# battery-board.net
KiCad netlist of a schematic drawn in EAGLE
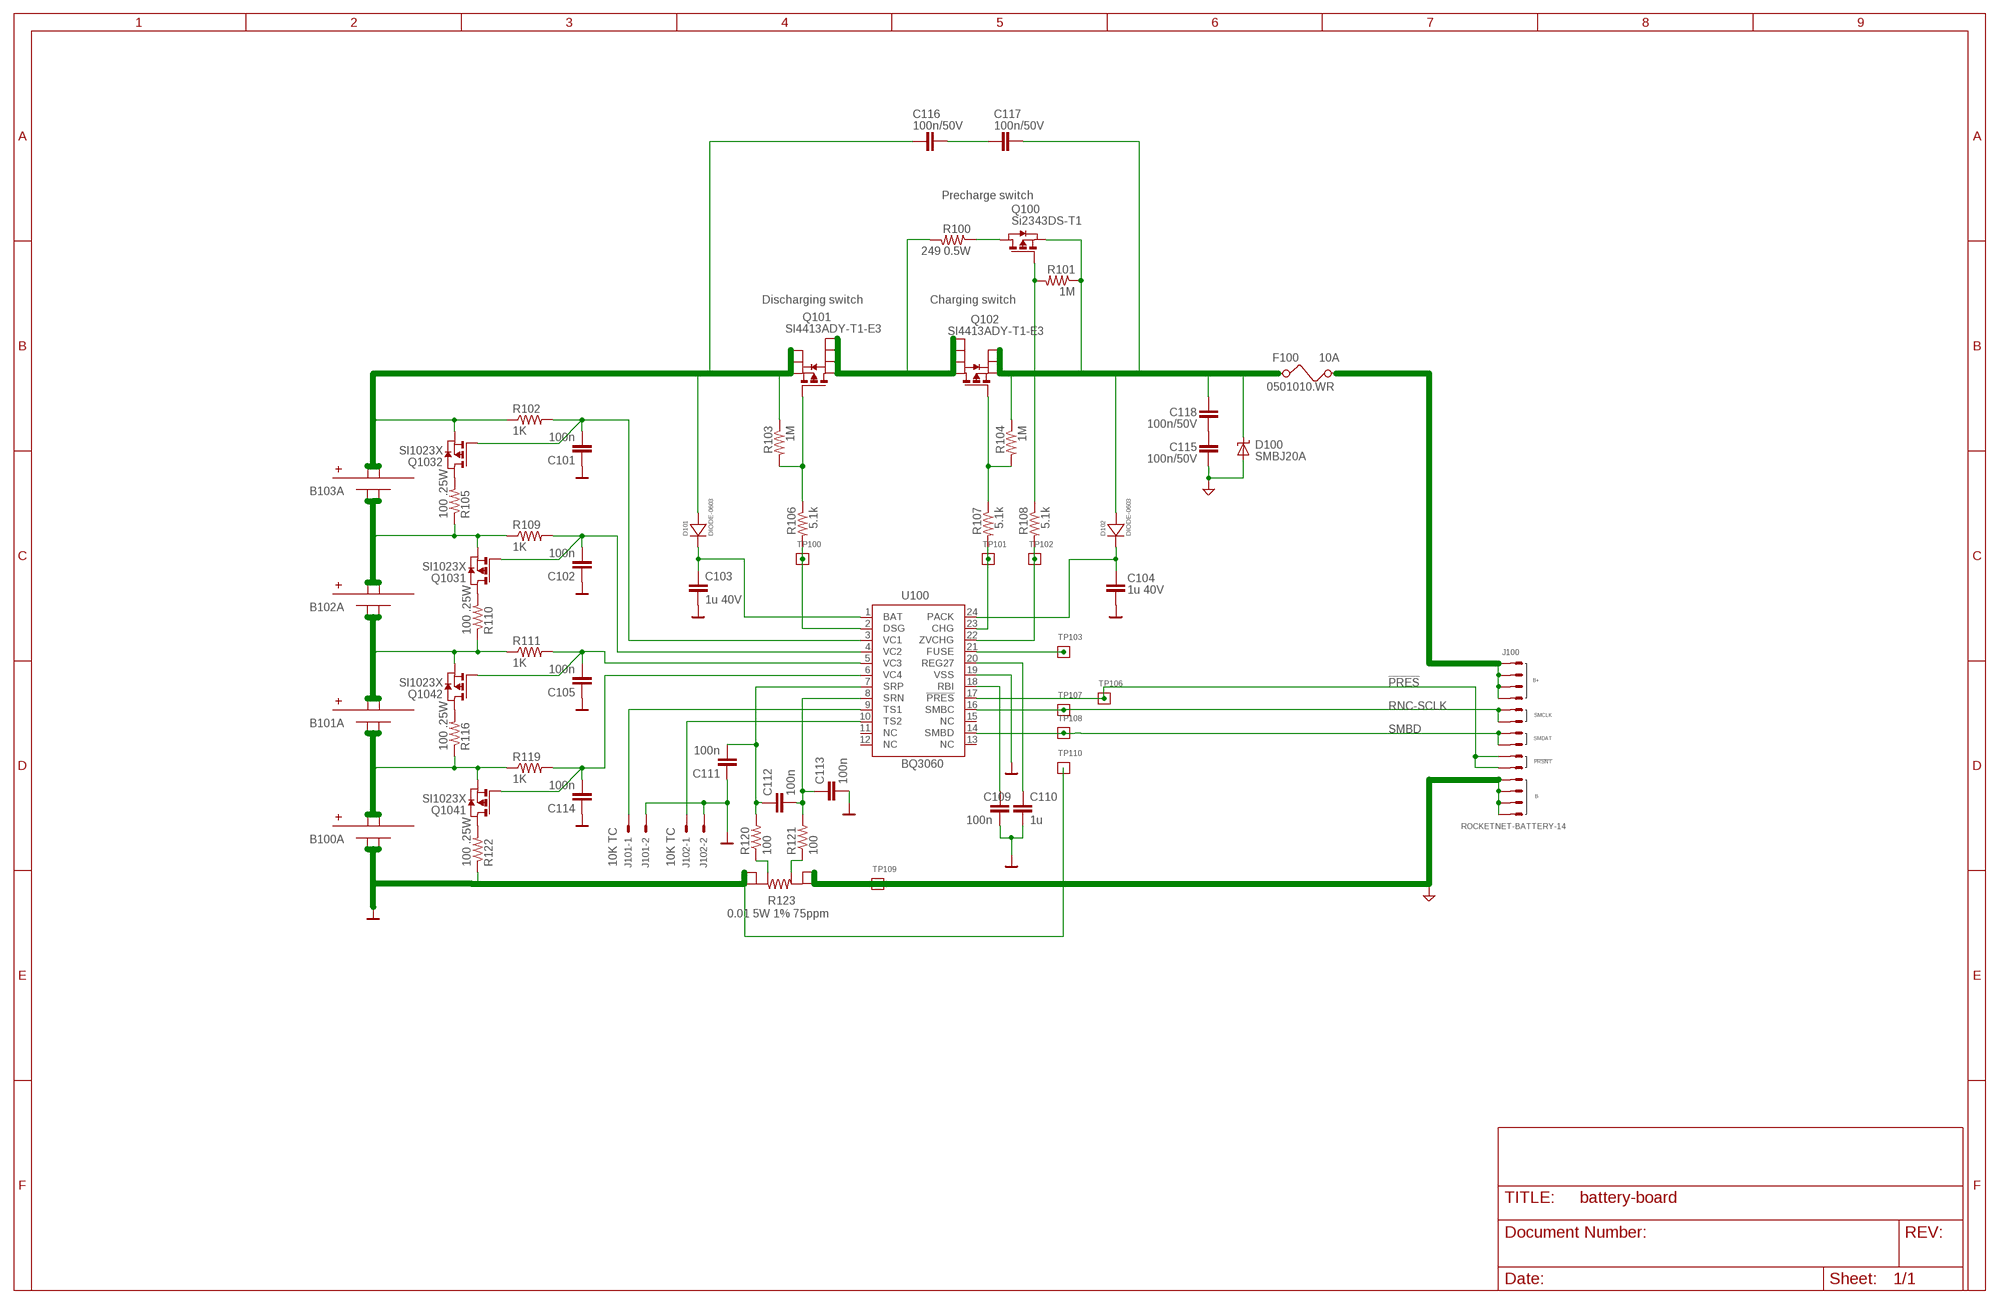
[diagram p0: schematic, sheet 1]

(export (version "E")
  (design (tool "Eeschema 10.0.6"))
  (components
    (comp (ref "B100A")
      (value "LIPO-8AHR")
      (footprint "eagle-import:LIPO-8AHR-PAC")
      (libsource (lib "eagle-import") (part "LIPO-8AHR"))
    )
    (comp (ref "B101A")
      (value "LIPO-8AHR")
      (footprint "eagle-import:LIPO-8AHR-PAC")
      (libsource (lib "eagle-import") (part "LIPO-8AHR"))
    )
    (comp (ref "B102A")
      (value "LIPO-8AHR")
      (footprint "eagle-import:LIPO-8AHR-PAC")
      (libsource (lib "eagle-import") (part "LIPO-8AHR"))
    )
    (comp (ref "B103A")
      (value "LIPO-8AHR")
      (footprint "eagle-import:LIPO-8AHR-PAC")
      (libsource (lib "eagle-import") (part "LIPO-8AHR"))
    )
    (comp (ref "C101")
      (value "100n")
      (footprint "eagle-import:0603-B-NOSILK")
      (libsource (lib "eagle-import") (part "C-EU0603-B-NOSILK"))
    )
    (comp (ref "C102")
      (value "100n")
      (footprint "eagle-import:0603-B-NOSILK")
      (libsource (lib "eagle-import") (part "C-EU0603-B-NOSILK"))
    )
    (comp (ref "C103")
      (value "1u 40V")
      (footprint "eagle-import:0603-B-NOSILK")
      (libsource (lib "eagle-import") (part "C-EU0603-B-NOSILK"))
    )
    (comp (ref "C104")
      (value "1u 40V")
      (footprint "eagle-import:0603-B-NOSILK")
      (libsource (lib "eagle-import") (part "C-EU0603-B-NOSILK"))
    )
    (comp (ref "C105")
      (value "100n")
      (footprint "eagle-import:0603-B-NOSILK")
      (libsource (lib "eagle-import") (part "C-EU0603-B-NOSILK"))
    )
    (comp (ref "C109")
      (value "100n")
      (footprint "eagle-import:0603-B-NOSILK")
      (libsource (lib "eagle-import") (part "C-EU0603-B-NOSILK"))
    )
    (comp (ref "C110")
      (value "1u")
      (footprint "eagle-import:0603-B-NOSILK")
      (libsource (lib "eagle-import") (part "C-EU0603-B-NOSILK"))
    )
    (comp (ref "C111")
      (value "100n")
      (footprint "eagle-import:0603-B-NOSILK")
      (libsource (lib "eagle-import") (part "C-EU0603-B-NOSILK"))
    )
    (comp (ref "C112")
      (value "100n")
      (footprint "eagle-import:0603-B-NOSILK")
      (libsource (lib "eagle-import") (part "C-EU0603-B-NOSILK"))
    )
    (comp (ref "C113")
      (value "100n")
      (footprint "eagle-import:0603-B-NOSILK")
      (libsource (lib "eagle-import") (part "C-EU0603-B-NOSILK"))
    )
    (comp (ref "C114")
      (value "100n")
      (footprint "eagle-import:0603-B-NOSILK")
      (libsource (lib "eagle-import") (part "C-EU0603-B-NOSILK"))
    )
    (comp (ref "C115")
      (value "100n/50V")
      (footprint "eagle-import:0603-B-NOSILK")
      (libsource (lib "eagle-import") (part "C-EU0603-B-NOSILK"))
    )
    (comp (ref "C116")
      (value "100n/50V")
      (footprint "eagle-import:0603-B-NOSILK")
      (libsource (lib "eagle-import") (part "C-EU0603-B-NOSILK"))
    )
    (comp (ref "C117")
      (value "100n/50V")
      (footprint "eagle-import:0603-B-NOSILK")
      (libsource (lib "eagle-import") (part "C-EU0603-B-NOSILK"))
    )
    (comp (ref "C118")
      (value "100n/50V")
      (footprint "eagle-import:0603-B-NOSILK")
      (libsource (lib "eagle-import") (part "C-EU0603-B-NOSILK"))
    )
    (comp (ref "D100")
      (value "SMBJ20A")
      (footprint "eagle-import:SMBJ")
      (libsource (lib "eagle-import") (part "SUPPRESSOR-SMBJ"))
    )
    (comp (ref "D101")
      (value "DIODE-0603")
      (footprint "eagle-import:0603-B-NOSILK-DIODE")
      (libsource (lib "eagle-import") (part "DIODE-0603"))
    )
    (comp (ref "D102")
      (value "DIODE-0603")
      (footprint "eagle-import:0603-B-NOSILK-DIODE")
      (libsource (lib "eagle-import") (part "DIODE-0603"))
    )
    (comp (ref "F100")
      (value "0501010.WR")
      (footprint "eagle-import:1206")
      (fields (field (name "DK") "F2919CT-ND"))
      (libsource (lib "eagle-import") (part "FUSE1206"))
    )
    (comp (ref "J100")
      (value "ROCKETNET-BATTERY-14")
      (footprint "eagle-import:ROCKETNET-M-14")
      (libsource (lib "eagle-import") (part "ROCKETNET-BATTERY-14"))
    )
    (comp (ref "J101")
      (value "87758-0216")
      (footprint "eagle-import:87758-0216")
      (libsource (lib "eagle-import") (part "87758-0216"))
    )
    (comp (ref "J102")
      (value "87758-0216")
      (footprint "eagle-import:87758-0216")
      (libsource (lib "eagle-import") (part "87758-0216"))
    )
    (comp (ref "Q100")
      (value "Si2343DS-T1")
      (footprint "eagle-import:SOT23")
      (libsource (lib "eagle-import") (part "NTR4101P"))
    )
    (comp (ref "Q101")
      (value "SI4413ADY-T1-E3")
      (footprint "eagle-import:SO-8")
      (libsource (lib "eagle-import") (part "SI4435DDY"))
    )
    (comp (ref "Q102")
      (value "SI4413ADY-T1-E3")
      (footprint "eagle-import:SO-8")
      (libsource (lib "eagle-import") (part "SI4435DDY"))
    )
    (comp (ref "Q103")
      (value "SI1023X")
      (footprint "eagle-import:SOT-563")
      (libsource (lib "eagle-import") (part "SI1023X"))
    )
    (comp (ref "Q104")
      (value "SI1023X")
      (footprint "eagle-import:SOT-563")
      (libsource (lib "eagle-import") (part "SI1023X"))
    )
    (comp (ref "R100")
      (value "249 0.5W")
      (footprint "eagle-import:1206-B")
      (libsource (lib "eagle-import") (part "R-US_1206-B"))
    )
    (comp (ref "R101")
      (value "1M")
      (footprint "eagle-import:0603-B-NOSILK")
      (libsource (lib "eagle-import") (part "R-US_0603-B-NOSILK"))
    )
    (comp (ref "R102")
      (value "1K")
      (footprint "eagle-import:0603-B-NOSILK")
      (libsource (lib "eagle-import") (part "R-US_0603-B-NOSILK"))
    )
    (comp (ref "R103")
      (value "1M")
      (footprint "eagle-import:0603-B-NOSILK")
      (libsource (lib "eagle-import") (part "R-US_0603-B-NOSILK"))
    )
    (comp (ref "R104")
      (value "1M")
      (footprint "eagle-import:0603-B-NOSILK")
      (libsource (lib "eagle-import") (part "R-US_0603-B-NOSILK"))
    )
    (comp (ref "R105")
      (value "100 .25W")
      (footprint "eagle-import:0603-B-NOSILK")
      (libsource (lib "eagle-import") (part "R-US_0603-B-NOSILK"))
    )
    (comp (ref "R106")
      (value "5.1k")
      (footprint "eagle-import:0603-B-NOSILK")
      (libsource (lib "eagle-import") (part "R-US_0603-B-NOSILK"))
    )
    (comp (ref "R107")
      (value "5.1k")
      (footprint "eagle-import:0603-B-NOSILK")
      (libsource (lib "eagle-import") (part "R-US_0603-B-NOSILK"))
    )
    (comp (ref "R108")
      (value "5.1k")
      (footprint "eagle-import:0603-B-NOSILK")
      (libsource (lib "eagle-import") (part "R-US_0603-B-NOSILK"))
    )
    (comp (ref "R109")
      (value "1K")
      (footprint "eagle-import:0603-B-NOSILK")
      (libsource (lib "eagle-import") (part "R-US_0603-B-NOSILK"))
    )
    (comp (ref "R110")
      (value "100 .25W")
      (footprint "eagle-import:0603-B-NOSILK")
      (libsource (lib "eagle-import") (part "R-US_0603-B-NOSILK"))
    )
    (comp (ref "R111")
      (value "1K")
      (footprint "eagle-import:0603-B-NOSILK")
      (libsource (lib "eagle-import") (part "R-US_0603-B-NOSILK"))
    )
    (comp (ref "R116")
      (value "100 .25W")
      (footprint "eagle-import:0603-B-NOSILK")
      (libsource (lib "eagle-import") (part "R-US_0603-B-NOSILK"))
    )
    (comp (ref "R119")
      (value "1K")
      (footprint "eagle-import:0603-B-NOSILK")
      (libsource (lib "eagle-import") (part "R-US_0603-B-NOSILK"))
    )
    (comp (ref "R120")
      (value "100")
      (footprint "eagle-import:0603-B-NOSILK")
      (libsource (lib "eagle-import") (part "R-US_0603-B-NOSILK"))
    )
    (comp (ref "R121")
      (value "100")
      (footprint "eagle-import:0603-B-NOSILK")
      (libsource (lib "eagle-import") (part "R-US_0603-B-NOSILK"))
    )
    (comp (ref "R122")
      (value "100 .25W")
      (footprint "eagle-import:0603-B-NOSILK")
      (libsource (lib "eagle-import") (part "R-US_0603-B-NOSILK"))
    )
    (comp (ref "R123")
      (value "0.01 5W 1% 75ppm")
      (footprint "eagle-import:VISHAY-2818")
      (libsource (lib "eagle-import") (part "R-US-2818"))
    )
    (comp (ref "TP100")
      (value "TEST-POINT")
      (footprint "eagle-import:2MM-TEST-POINT")
      (libsource (lib "eagle-import") (part "TEST-POINT"))
    )
    (comp (ref "TP101")
      (value "TEST-POINT")
      (footprint "eagle-import:2MM-TEST-POINT")
      (libsource (lib "eagle-import") (part "TEST-POINT"))
    )
    (comp (ref "TP102")
      (value "TEST-POINT")
      (footprint "eagle-import:2MM-TEST-POINT")
      (libsource (lib "eagle-import") (part "TEST-POINT"))
    )
    (comp (ref "TP103")
      (value "TEST-POINT")
      (footprint "eagle-import:2MM-TEST-POINT")
      (libsource (lib "eagle-import") (part "TEST-POINT"))
    )
    (comp (ref "TP106")
      (value "TEST-POINT")
      (footprint "eagle-import:2MM-TEST-POINT")
      (libsource (lib "eagle-import") (part "TEST-POINT"))
    )
    (comp (ref "TP107")
      (value "TEST-POINT")
      (footprint "eagle-import:2MM-TEST-POINT")
      (libsource (lib "eagle-import") (part "TEST-POINT"))
    )
    (comp (ref "TP108")
      (value "TEST-POINT")
      (footprint "eagle-import:2MM-TEST-POINT")
      (libsource (lib "eagle-import") (part "TEST-POINT"))
    )
    (comp (ref "TP109")
      (value "TEST-POINT")
      (footprint "eagle-import:2MM-TEST-POINT")
      (libsource (lib "eagle-import") (part "TEST-POINT"))
    )
    (comp (ref "TP110")
      (value "TEST-POINT")
      (footprint "eagle-import:2MM-TEST-POINT")
      (libsource (lib "eagle-import") (part "TEST-POINT"))
    )
    (comp (ref "U100")
      (value "BQ3060PW")
      (footprint "eagle-import:PW-R-PDSO-G24")
      (libsource (lib "eagle-import") (part "BQ3060PW"))
    )
  )
  (nets
    (net (code "1") (name "/RNC-SCLK") (class "Default")
      (node (ref "J100") (pin "SMCLK@3") (pinfunction "SMCLK_SMCLK@3") (pintype "passive"))
      (node (ref "J100") (pin "SMCLK@4") (pinfunction "SMCLK_SMCLK@4") (pintype "passive"))
      (node (ref "TP107") (pin "1") (pinfunction "P$1_1") (pintype "passive"))
      (node (ref "U100") (pin "16") (pinfunction "SMBC_16") (pintype "bidirectional"))
    )
    (net (code "2") (name "/SMBD") (class "Default")
      (node (ref "J100") (pin "SMDAT@7") (pinfunction "SMDAT_SMDAT@7") (pintype "passive"))
      (node (ref "J100") (pin "SMDAT@8") (pinfunction "SMDAT_SMDAT@8") (pintype "passive"))
      (node (ref "TP108") (pin "1") (pinfunction "P$1_1") (pintype "passive"))
      (node (ref "U100") (pin "14") (pinfunction "SMBD_14") (pintype "bidirectional"))
    )
    (net (code "3") (name "/~{PRES}") (class "Default")
      (node (ref "J100") (pin "!PRSNT@10") (pinfunction "~{PRSNT}_!PRSNT@10") (pintype "passive"))
      (node (ref "J100") (pin "!PRSNT@9") (pinfunction "~{PRSNT}_!PRSNT@9") (pintype "passive"))
      (node (ref "TP106") (pin "1") (pinfunction "P$1_1") (pintype "passive"))
      (node (ref "U100") (pin "17") (pinfunction "~{PRES}_17") (pintype "input"))
    )
    (net (code "4") (name "Net-(C115-Pad1)") (class "Default")
      (node (ref "C115") (pin "1") (pinfunction "1_1") (pintype "passive"))
      (node (ref "C118") (pin "2") (pinfunction "2_2") (pintype "passive"))
    )
    (net (code "5") (name "Net-(C116-Pad2)") (class "Default")
      (node (ref "C116") (pin "2") (pinfunction "2_2") (pintype "passive"))
      (node (ref "C117") (pin "1") (pinfunction "1_1") (pintype "passive"))
    )
    (net (code "6") (name "Net-(F100-Pad1)") (class "Default")
      (node (ref "F100") (pin "1") (pinfunction "1_1") (pintype "passive"))
      (node (ref "J100") (pin "B+@1") (pinfunction "B+_B+@1") (pintype "power_in"))
      (node (ref "J100") (pin "B+@2") (pinfunction "B+_B+@2") (pintype "power_in"))
      (node (ref "J100") (pin "B+@3") (pinfunction "B+_B+@3") (pintype "passive"))
      (node (ref "J100") (pin "B+@4") (pinfunction "B+_B+@4") (pintype "passive"))
    )
    (net (code "7") (name "Net-(J101A-S)") (class "Default")
      (node (ref "J101") (pin "1") (pinfunction "S_1") (pintype "passive"))
      (node (ref "U100") (pin "9") (pinfunction "TS1_9") (pintype "input"))
    )
    (net (code "8") (name "Net-(J102A-S)") (class "Default")
      (node (ref "J102") (pin "1") (pinfunction "S_1") (pintype "passive"))
      (node (ref "U100") (pin "10") (pinfunction "TS2_10") (pintype "input"))
    )
    (net (code "9") (name "Net-(Q100-D)") (class "Default")
      (node (ref "Q100") (pin "3") (pinfunction "D_3") (pintype "passive"))
      (node (ref "R100") (pin "1") (pinfunction "1_1") (pintype "passive"))
    )
    (net (code "10") (name "Net-(Q100-G)") (class "Default")
      (node (ref "Q100") (pin "1") (pinfunction "G_1") (pintype "passive"))
      (node (ref "R101") (pin "2") (pinfunction "2_2") (pintype "passive"))
      (node (ref "R108") (pin "1") (pinfunction "1_1") (pintype "passive"))
    )
    (net (code "11") (name "Net-(Q100-S)") (class "Default")
      (node (ref "C117") (pin "2") (pinfunction "2_2") (pintype "passive"))
      (node (ref "C118") (pin "1") (pinfunction "1_1") (pintype "passive"))
      (node (ref "D100") (pin "C") (pinfunction "C_C") (pintype "passive"))
      (node (ref "D102") (pin "ANODE") (pinfunction "ANODE_ANODE") (pintype "passive"))
      (node (ref "F100") (pin "2") (pinfunction "2_2") (pintype "passive"))
      (node (ref "Q100") (pin "2") (pinfunction "S_2") (pintype "passive"))
      (node (ref "Q102") (pin "1") (pinfunction "S_1") (pintype "passive"))
      (node (ref "Q102") (pin "2") (pinfunction "S_2") (pintype "passive"))
      (node (ref "Q102") (pin "3") (pinfunction "S_3") (pintype "passive"))
      (node (ref "R101") (pin "1") (pinfunction "1_1") (pintype "passive"))
      (node (ref "R104") (pin "1") (pinfunction "1_1") (pintype "passive"))
    )
    (net (code "12") (name "Net-(Q101-D-Pad5)") (class "Default")
      (node (ref "Q101") (pin "5") (pinfunction "D_5") (pintype "passive"))
      (node (ref "Q101") (pin "6") (pinfunction "D_6") (pintype "passive"))
      (node (ref "Q101") (pin "7") (pinfunction "D_7") (pintype "passive"))
      (node (ref "Q101") (pin "8") (pinfunction "D_8") (pintype "passive"))
      (node (ref "Q102") (pin "5") (pinfunction "D_5") (pintype "passive"))
      (node (ref "Q102") (pin "6") (pinfunction "D_6") (pintype "passive"))
      (node (ref "Q102") (pin "7") (pinfunction "D_7") (pintype "passive"))
      (node (ref "Q102") (pin "8") (pinfunction "D_8") (pintype "passive"))
      (node (ref "R100") (pin "2") (pinfunction "2_2") (pintype "passive"))
    )
    (net (code "13") (name "Net-(Q101-G)") (class "Default")
      (node (ref "Q101") (pin "4") (pinfunction "G_4") (pintype "passive"))
      (node (ref "R103") (pin "2") (pinfunction "2_2") (pintype "passive"))
      (node (ref "R106") (pin "1") (pinfunction "1_1") (pintype "passive"))
    )
    (net (code "14") (name "Net-(Q102-G)") (class "Default")
      (node (ref "Q102") (pin "4") (pinfunction "G_4") (pintype "passive"))
      (node (ref "R104") (pin "2") (pinfunction "2_2") (pintype "passive"))
      (node (ref "R107") (pin "1") (pinfunction "1_1") (pintype "passive"))
    )
    (net (code "15") (name "Net-(Q103A-D)") (class "Default")
      (node (ref "Q103") (pin "6") (pinfunction "D_6") (pintype "passive"))
      (node (ref "R110") (pin "2") (pinfunction "2_2") (pintype "passive"))
    )
    (net (code "16") (name "Net-(Q103A-G)") (class "Default")
      (node (ref "C102") (pin "2") (pinfunction "2_2") (pintype "passive"))
      (node (ref "Q103") (pin "2") (pinfunction "G_2") (pintype "passive"))
      (node (ref "R109") (pin "2") (pinfunction "2_2") (pintype "passive"))
      (node (ref "U100") (pin "4") (pinfunction "VC2_4") (pintype "input"))
    )
    (net (code "17") (name "Net-(Q103A-S)") (class "Default")
      (node (ref "B102A") (pin "B+@1") (pinfunction "B+_B+@1") (pintype "passive"))
      (node (ref "B102A") (pin "B+@2") (pinfunction "B+_B+@2") (pintype "passive"))
      (node (ref "B103A") (pin "B-@1") (pinfunction "B-_B-@1") (pintype "passive"))
      (node (ref "B103A") (pin "B-@2") (pinfunction "B-_B-@2") (pintype "passive"))
      (node (ref "Q103") (pin "1") (pinfunction "S_1") (pintype "passive"))
      (node (ref "R105") (pin "1") (pinfunction "1_1") (pintype "passive"))
      (node (ref "R109") (pin "1") (pinfunction "1_1") (pintype "passive"))
    )
    (net (code "18") (name "Net-(Q103B-D)") (class "Default")
      (node (ref "Q103") (pin "3") (pinfunction "D_3") (pintype "passive"))
      (node (ref "R105") (pin "2") (pinfunction "2_2") (pintype "passive"))
    )
    (net (code "19") (name "Net-(Q103B-G)") (class "Default")
      (node (ref "C101") (pin "2") (pinfunction "2_2") (pintype "passive"))
      (node (ref "Q103") (pin "5") (pinfunction "G_5") (pintype "passive"))
      (node (ref "R102") (pin "2") (pinfunction "2_2") (pintype "passive"))
      (node (ref "U100") (pin "3") (pinfunction "VC1_3") (pintype "input"))
    )
    (net (code "20") (name "Net-(Q103B-S)") (class "Default")
      (node (ref "B103A") (pin "B+@1") (pinfunction "B+_B+@1") (pintype "passive"))
      (node (ref "B103A") (pin "B+@2") (pinfunction "B+_B+@2") (pintype "passive"))
      (node (ref "C116") (pin "1") (pinfunction "1_1") (pintype "passive"))
      (node (ref "D101") (pin "ANODE") (pinfunction "ANODE_ANODE") (pintype "passive"))
      (node (ref "Q101") (pin "1") (pinfunction "S_1") (pintype "passive"))
      (node (ref "Q101") (pin "2") (pinfunction "S_2") (pintype "passive"))
      (node (ref "Q101") (pin "3") (pinfunction "S_3") (pintype "passive"))
      (node (ref "Q103") (pin "4") (pinfunction "S_4") (pintype "passive"))
      (node (ref "R102") (pin "1") (pinfunction "1_1") (pintype "passive"))
      (node (ref "R103") (pin "1") (pinfunction "1_1") (pintype "passive"))
    )
    (net (code "21") (name "Net-(Q104A-D)") (class "Default")
      (node (ref "Q104") (pin "6") (pinfunction "D_6") (pintype "passive"))
      (node (ref "R122") (pin "2") (pinfunction "2_2") (pintype "passive"))
    )
    (net (code "22") (name "Net-(Q104A-G)") (class "Default")
      (node (ref "C114") (pin "2") (pinfunction "2_2") (pintype "passive"))
      (node (ref "Q104") (pin "2") (pinfunction "G_2") (pintype "passive"))
      (node (ref "R119") (pin "2") (pinfunction "2_2") (pintype "passive"))
      (node (ref "U100") (pin "6") (pinfunction "VC4_6") (pintype "input"))
    )
    (net (code "23") (name "Net-(Q104A-S)") (class "Default")
      (node (ref "B100A") (pin "B+@1") (pinfunction "B+_B+@1") (pintype "passive"))
      (node (ref "B100A") (pin "B+@2") (pinfunction "B+_B+@2") (pintype "passive"))
      (node (ref "B101A") (pin "B-@1") (pinfunction "B-_B-@1") (pintype "passive"))
      (node (ref "B101A") (pin "B-@2") (pinfunction "B-_B-@2") (pintype "passive"))
      (node (ref "Q104") (pin "1") (pinfunction "S_1") (pintype "passive"))
      (node (ref "R116") (pin "1") (pinfunction "1_1") (pintype "passive"))
      (node (ref "R119") (pin "1") (pinfunction "1_1") (pintype "passive"))
    )
    (net (code "24") (name "Net-(Q104B-D)") (class "Default")
      (node (ref "Q104") (pin "3") (pinfunction "D_3") (pintype "passive"))
      (node (ref "R116") (pin "2") (pinfunction "2_2") (pintype "passive"))
    )
    (net (code "25") (name "Net-(Q104B-G)") (class "Default")
      (node (ref "C105") (pin "2") (pinfunction "2_2") (pintype "passive"))
      (node (ref "Q104") (pin "5") (pinfunction "G_5") (pintype "passive"))
      (node (ref "R111") (pin "2") (pinfunction "2_2") (pintype "passive"))
      (node (ref "U100") (pin "5") (pinfunction "VC3_5") (pintype "input"))
    )
    (net (code "26") (name "Net-(Q104B-S)") (class "Default")
      (node (ref "B101A") (pin "B+@1") (pinfunction "B+_B+@1") (pintype "passive"))
      (node (ref "B101A") (pin "B+@2") (pinfunction "B+_B+@2") (pintype "passive"))
      (node (ref "B102A") (pin "B-@1") (pinfunction "B-_B-@1") (pintype "passive"))
      (node (ref "B102A") (pin "B-@2") (pinfunction "B-_B-@2") (pintype "passive"))
      (node (ref "Q104") (pin "4") (pinfunction "S_4") (pintype "passive"))
      (node (ref "R110") (pin "1") (pinfunction "1_1") (pintype "passive"))
      (node (ref "R111") (pin "1") (pinfunction "1_1") (pintype "passive"))
    )
    (net (code "27") (name "Net-(R120-Pad1)") (class "Default")
      (node (ref "R120") (pin "1") (pinfunction "1_1") (pintype "passive"))
      (node (ref "R123") (pin "K1") (pinfunction "K1_K1") (pintype "passive"))
    )
    (net (code "28") (name "Net-(R121-Pad1)") (class "Default")
      (node (ref "R121") (pin "1") (pinfunction "1_1") (pintype "passive"))
      (node (ref "R123") (pin "K2") (pinfunction "K2_K2") (pintype "passive"))
    )
    (net (code "29") (name "Net-(TP100-P$1)") (class "Default")
      (node (ref "R106") (pin "2") (pinfunction "2_2") (pintype "passive"))
      (node (ref "TP100") (pin "1") (pinfunction "P$1_1") (pintype "passive"))
      (node (ref "U100") (pin "2") (pinfunction "DSG_2") (pintype "output"))
    )
    (net (code "30") (name "Net-(TP101-P$1)") (class "Default")
      (node (ref "R107") (pin "2") (pinfunction "2_2") (pintype "passive"))
      (node (ref "TP101") (pin "1") (pinfunction "P$1_1") (pintype "passive"))
      (node (ref "U100") (pin "23") (pinfunction "CHG_23") (pintype "output"))
    )
    (net (code "31") (name "Net-(TP102-P$1)") (class "Default")
      (node (ref "R108") (pin "2") (pinfunction "2_2") (pintype "passive"))
      (node (ref "TP102") (pin "1") (pinfunction "P$1_1") (pintype "passive"))
      (node (ref "U100") (pin "22") (pinfunction "ZVCHG_22") (pintype "output"))
    )
    (net (code "32") (name "Net-(TP103-P$1)") (class "Default")
      (node (ref "TP103") (pin "1") (pinfunction "P$1_1") (pintype "passive"))
      (node (ref "U100") (pin "21") (pinfunction "FUSE_21") (pintype "bidirectional"))
    )
    (net (code "33") (name "Net-(U100-BAT)") (class "Default")
      (node (ref "C103") (pin "1") (pinfunction "1_1") (pintype "passive"))
      (node (ref "D101") (pin "CATHODE") (pinfunction "CATHODE_CATHODE") (pintype "passive"))
      (node (ref "U100") (pin "1") (pinfunction "BAT_1") (pintype "power_in"))
    )
    (net (code "34") (name "Net-(U100-PACK)") (class "Default")
      (node (ref "C104") (pin "1") (pinfunction "1_1") (pintype "passive"))
      (node (ref "D102") (pin "CATHODE") (pinfunction "CATHODE_CATHODE") (pintype "passive"))
      (node (ref "U100") (pin "24") (pinfunction "PACK_24") (pintype "power_in"))
    )
    (net (code "35") (name "Net-(U100-RBI)") (class "Default")
      (node (ref "C109") (pin "1") (pinfunction "1_1") (pintype "passive"))
      (node (ref "U100") (pin "18") (pinfunction "RBI_18") (pintype "power_in"))
    )
    (net (code "36") (name "Net-(U100-REG27)") (class "Default")
      (node (ref "C110") (pin "1") (pinfunction "1_1") (pintype "passive"))
      (node (ref "U100") (pin "20") (pinfunction "REG27_20") (pintype "power_in"))
    )
    (net (code "37") (name "Net-(U100-SRN)") (class "Default")
      (node (ref "C112") (pin "2") (pinfunction "2_2") (pintype "passive"))
      (node (ref "C113") (pin "1") (pinfunction "1_1") (pintype "passive"))
      (node (ref "R121") (pin "2") (pinfunction "2_2") (pintype "passive"))
      (node (ref "U100") (pin "8") (pinfunction "SRN_8") (pintype "input"))
    )
    (net (code "38") (name "Net-(U100-SRP)") (class "Default")
      (node (ref "C111") (pin "2") (pinfunction "2_2") (pintype "passive"))
      (node (ref "C112") (pin "1") (pinfunction "1_1") (pintype "passive"))
      (node (ref "R120") (pin "2") (pinfunction "2_2") (pintype "passive"))
      (node (ref "U100") (pin "7") (pinfunction "SRP_7") (pintype "input"))
    )
    (net (code "39") (name "SUP_GND_BAR") (class "Default")
      (node (ref "B100A") (pin "B-@1") (pinfunction "B-_B-@1") (pintype "passive"))
      (node (ref "B100A") (pin "B-@2") (pinfunction "B-_B-@2") (pintype "passive"))
      (node (ref "C101") (pin "1") (pinfunction "1_1") (pintype "passive"))
      (node (ref "C102") (pin "1") (pinfunction "1_1") (pintype "passive"))
      (node (ref "C103") (pin "2") (pinfunction "2_2") (pintype "passive"))
      (node (ref "C104") (pin "2") (pinfunction "2_2") (pintype "passive"))
      (node (ref "C105") (pin "1") (pinfunction "1_1") (pintype "passive"))
      (node (ref "C109") (pin "2") (pinfunction "2_2") (pintype "passive"))
      (node (ref "C110") (pin "2") (pinfunction "2_2") (pintype "passive"))
      (node (ref "C111") (pin "1") (pinfunction "1_1") (pintype "passive"))
      (node (ref "C113") (pin "2") (pinfunction "2_2") (pintype "passive"))
      (node (ref "C114") (pin "1") (pinfunction "1_1") (pintype "passive"))
      (node (ref "J101") (pin "2") (pinfunction "S_2") (pintype "passive"))
      (node (ref "J102") (pin "2") (pinfunction "S_2") (pintype "passive"))
      (node (ref "R122") (pin "1") (pinfunction "1_1") (pintype "passive"))
      (node (ref "R123") (pin "1@1") (pinfunction "1_1@1") (pintype "passive"))
      (node (ref "R123") (pin "1@2") (pinfunction "1_1@2") (pintype "passive"))
      (node (ref "TP110") (pin "1") (pinfunction "P$1_1") (pintype "passive"))
      (node (ref "U100") (pin "19") (pinfunction "VSS_19") (pintype "power_in"))
    )
    (net (code "40") (name "SUP_GND_TRIANGLE") (class "Default")
      (node (ref "C115") (pin "2") (pinfunction "2_2") (pintype "passive"))
      (node (ref "D100") (pin "A") (pinfunction "A_A") (pintype "passive"))
      (node (ref "J100") (pin "B-@11") (pinfunction "B-_B-@11") (pintype "passive"))
      (node (ref "J100") (pin "B-@12") (pinfunction "B-_B-@12") (pintype "passive"))
      (node (ref "J100") (pin "B-@13") (pinfunction "B-_B-@13") (pintype "passive"))
      (node (ref "J100") (pin "B-@14") (pinfunction "B-_B-@14") (pintype "passive"))
      (node (ref "R123") (pin "2@1") (pinfunction "2_2@1") (pintype "passive"))
      (node (ref "R123") (pin "2@2") (pinfunction "2_2@2") (pintype "passive"))
      (node (ref "TP109") (pin "1") (pinfunction "P$1_1") (pintype "passive"))
    )
    (net (code "41") (name "unconnected-(U100-NC-Pad11)") (class "Default")
      (node (ref "U100") (pin "11") (pinfunction "NC_11") (pintype "no_connect"))
    )
    (net (code "42") (name "unconnected-(U100-NC-Pad12)") (class "Default")
      (node (ref "U100") (pin "12") (pinfunction "NC_12") (pintype "no_connect"))
    )
    (net (code "43") (name "unconnected-(U100-NC-Pad13)") (class "Default")
      (node (ref "U100") (pin "13") (pinfunction "NC_13") (pintype "no_connect"))
    )
    (net (code "44") (name "unconnected-(U100-NC-Pad15)") (class "Default")
      (node (ref "U100") (pin "15") (pinfunction "NC_15") (pintype "no_connect"))
    )
  )
)
